# micICS40310.net
KiCad netlist of a schematic drawn in EAGLE
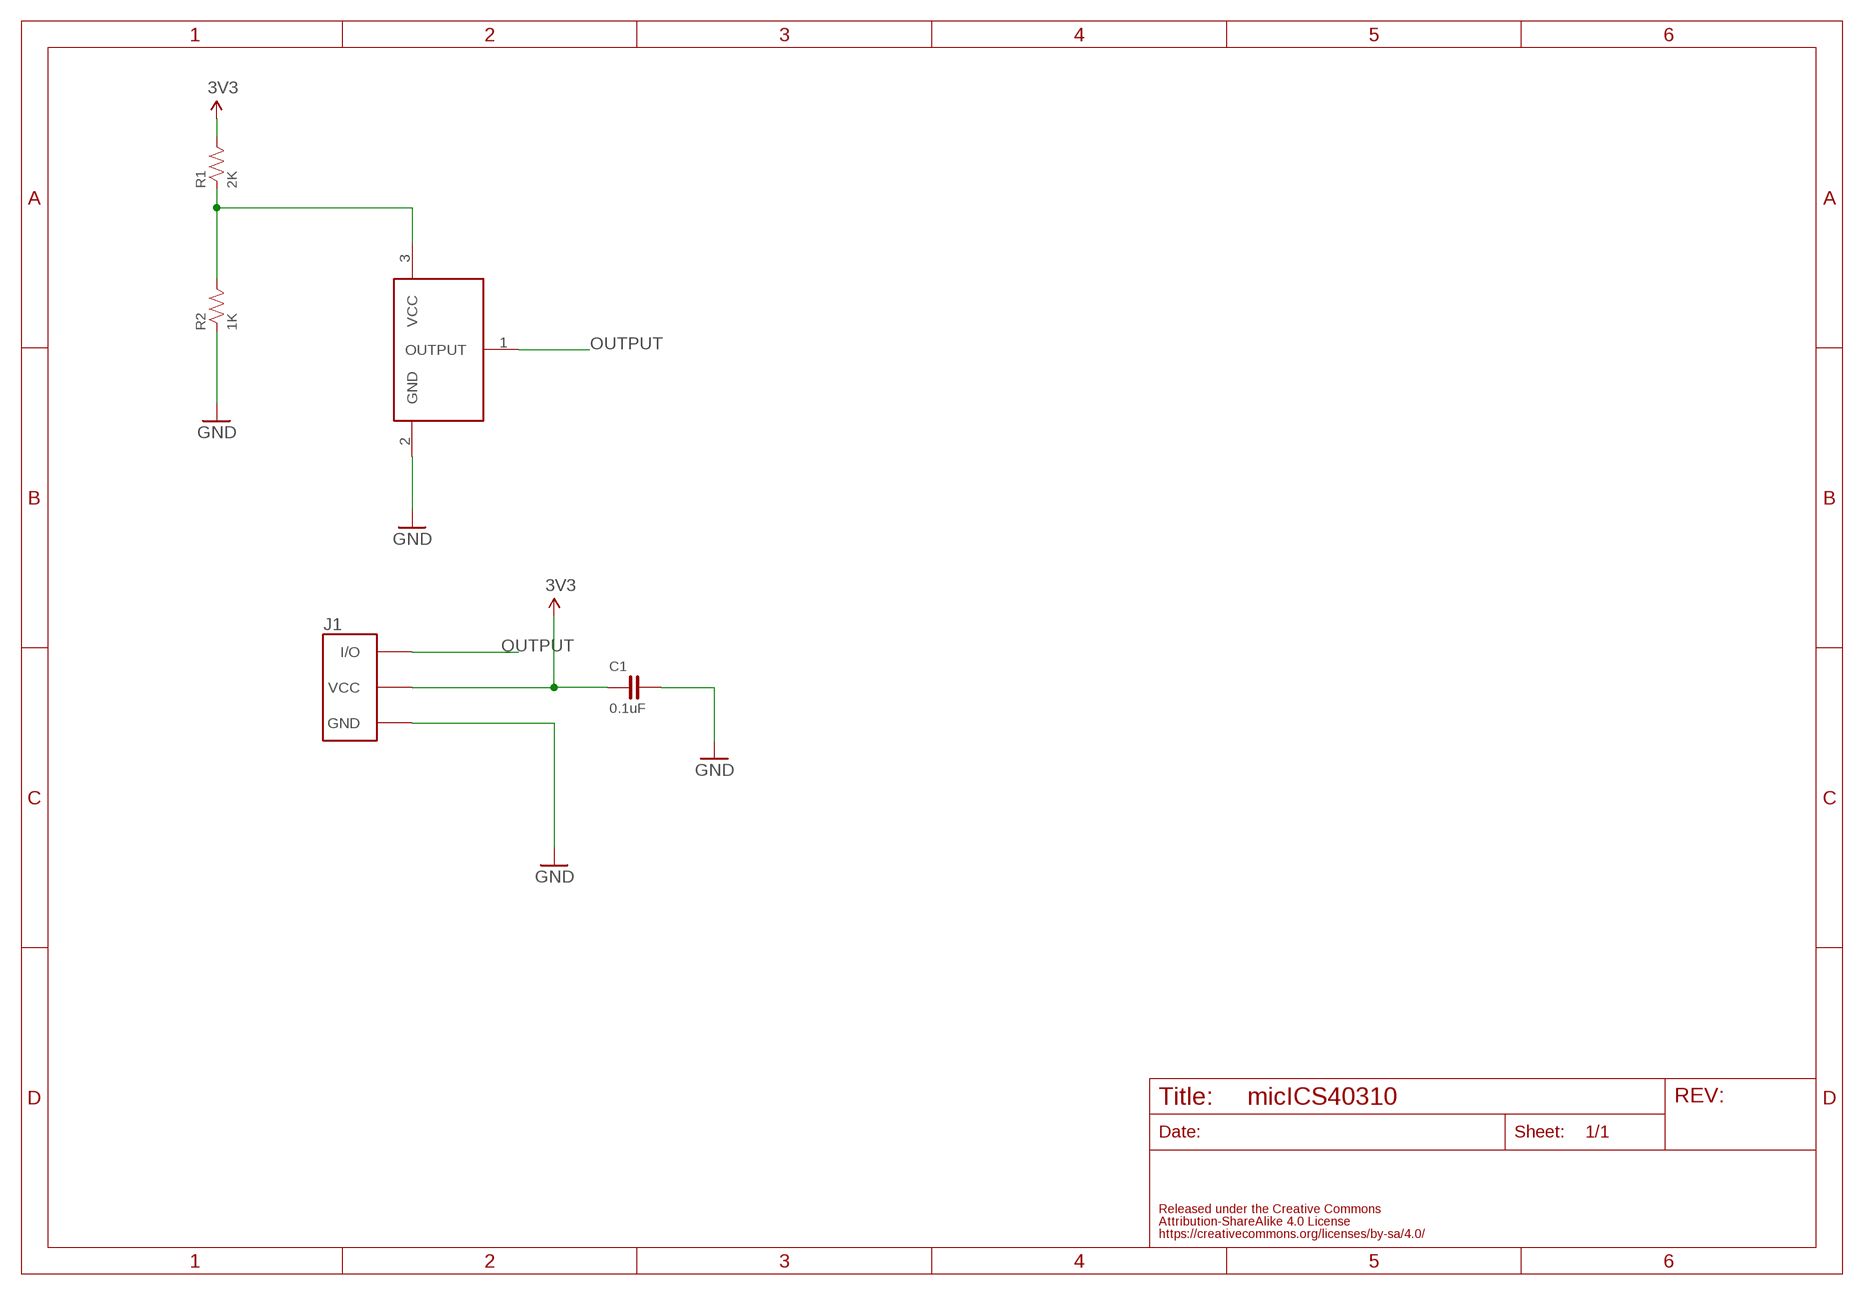
[diagram p0: schematic, sheet 1]

(export (version "E")
  (design (tool "Eeschema 10.0.6"))
  (components
    (comp (ref "C1")
      (value "0.1uF")
      (footprint "eagle-import:0603")
      (libsource (lib "eagle-import") (part "CAPACITOR-0603"))
    )
    (comp (ref "ICS40310")
      (value "ANALOG-MICICS40310")
      (footprint "eagle-import:ICS40310")
      (libsource (lib "eagle-import") (part "ANALOG-MICICS40310"))
    )
    (comp (ref "J1")
      (value "FABO_BRICK_3PIN-03B-PASK-1_NAME_BOTTOM")
      (footprint "eagle-import:FABO_BRICK_3PIN_B03B-PASK-1_NAME_BOTTOM")
      (libsource (lib "eagle-import") (part "FABO_BRICK_3PIN-03B-PASK-1_NAME_BOTTOM"))
    )
    (comp (ref "R1")
      (value "2K")
      (footprint "eagle-import:0603")
      (libsource (lib "eagle-import") (part "RESISTOR-0603"))
    )
    (comp (ref "R2")
      (value "1K")
      (footprint "eagle-import:0603")
      (libsource (lib "eagle-import") (part "RESISTOR-0603"))
    )
  )
  (nets
    (net (code "1") (name "/OUTPUT") (class "Default")
      (node (ref "ICS40310") (pin "1") (pinfunction "OUTPUT_1") (pintype "bidirectional"))
      (node (ref "J1") (pin "I/O") (pinfunction "I/O_I/O") (pintype "bidirectional"))
    )
    (net (code "2") (name "3V3") (class "Default")
      (node (ref "C1") (pin "1") (pinfunction "1_1") (pintype "passive"))
      (node (ref "J1") (pin "VCC") (pinfunction "VCC_VCC") (pintype "bidirectional"))
      (node (ref "R1") (pin "2") (pinfunction "2_2") (pintype "bidirectional"))
    )
    (net (code "3") (name "GND") (class "Default")
      (node (ref "C1") (pin "2") (pinfunction "2_2") (pintype "passive"))
      (node (ref "ICS40310") (pin "2") (pinfunction "GND_2") (pintype "bidirectional"))
      (node (ref "J1") (pin "GND") (pinfunction "GND_GND") (pintype "bidirectional"))
      (node (ref "R2") (pin "1") (pinfunction "1_1") (pintype "bidirectional"))
    )
    (net (code "4") (name "Net-(ICS40310-VCC)") (class "Default")
      (node (ref "ICS40310") (pin "3") (pinfunction "VCC_3") (pintype "bidirectional"))
      (node (ref "R1") (pin "1") (pinfunction "1_1") (pintype "bidirectional"))
      (node (ref "R2") (pin "2") (pinfunction "2_2") (pintype "bidirectional"))
    )
  )
)
